# HYPNOS_BOARD_SHIELD_V1.net
KiCad netlist of a schematic drawn in EAGLE
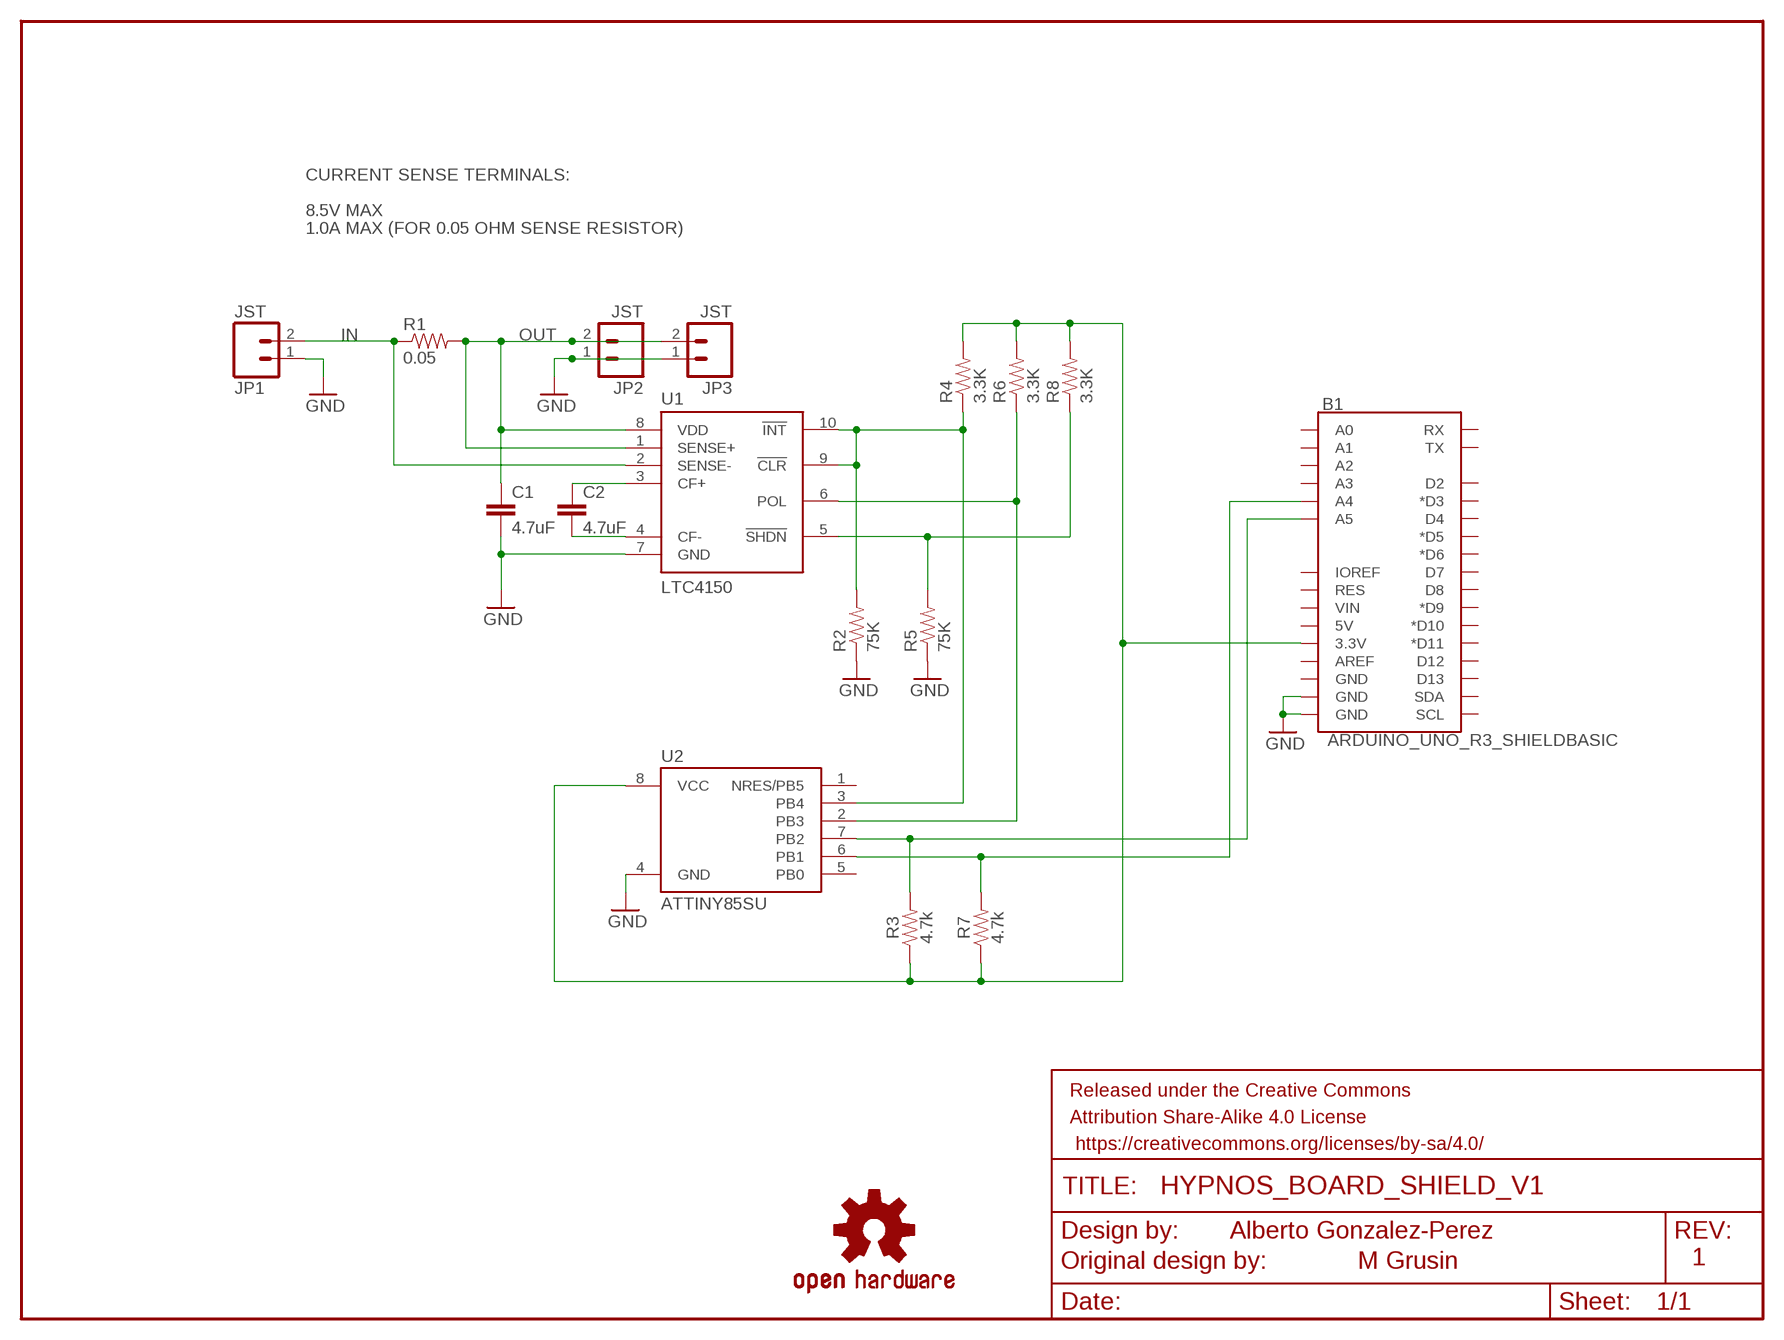
[diagram p0: schematic, sheet 1]

(export (version "E")
  (design (tool "Eeschema 10.0.6"))
  (components
    (comp (ref "B1")
      (value "ARDUINO_UNO_R3_SHIELDBASIC")
      (footprint "eagle-import:UNO_R3_SHIELD")
      (libsource (lib "eagle-import") (part "ARDUINO_UNO_R3_SHIELDBASIC"))
    )
    (comp (ref "C1")
      (value "4.7uF")
      (footprint "eagle-import:0603-CAP")
      (libsource (lib "eagle-import") (part "CAP0603-CAP"))
    )
    (comp (ref "C2")
      (value "4.7uF")
      (footprint "eagle-import:0603-CAP")
      (libsource (lib "eagle-import") (part "CAP0603-CAP"))
    )
    (comp (ref "FRAME1")
      (value "FRAME-LETTER")
      (footprint "eagle-import:CREATIVE_COMMONS")
      (libsource (lib "eagle-import") (part "FRAME-LETTER"))
    )
    (comp (ref "JP1")
      (value "JST")
      (footprint "eagle-import:JST-2-SMD")
      (libsource (lib "eagle-import") (part "M02-JST-2MM-SMT"))
    )
    (comp (ref "JP2")
      (value "JST")
      (footprint "eagle-import:JST-2-SMD")
      (libsource (lib "eagle-import") (part "M02-JST-2MM-SMT"))
    )
    (comp (ref "JP3")
      (value "JST")
      (footprint "eagle-import:JST-2-SMD")
      (libsource (lib "eagle-import") (part "M02-JST-2MM-SMT"))
    )
    (comp (ref "LOGO1")
      (value "OSHW-LOGOS")
      (footprint "eagle-import:OSHW-LOGO-S")
      (libsource (lib "eagle-import") (part "OSHW-LOGOS"))
    )
    (comp (ref "R1")
      (value "0.05")
      (footprint "eagle-import:1206")
      (libsource (lib "eagle-import") (part "RESISTOR1206"))
    )
    (comp (ref "R2")
      (value "75K")
      (footprint "eagle-import:0603-RES")
      (libsource (lib "eagle-import") (part "RESISTOR0603-RES"))
    )
    (comp (ref "R3")
      (value "4.7k")
      (footprint "eagle-import:0603")
      (libsource (lib "eagle-import") (part "4.7KOHM-0603-1/10W-1%"))
    )
    (comp (ref "R4")
      (value "3.3K")
      (footprint "eagle-import:0603-RES")
      (libsource (lib "eagle-import") (part "RESISTOR0603-RES"))
    )
    (comp (ref "R5")
      (value "75K")
      (footprint "eagle-import:0603-RES")
      (libsource (lib "eagle-import") (part "RESISTOR0603-RES"))
    )
    (comp (ref "R6")
      (value "3.3K")
      (footprint "eagle-import:0603-RES")
      (libsource (lib "eagle-import") (part "RESISTOR0603-RES"))
    )
    (comp (ref "R7")
      (value "4.7k")
      (footprint "eagle-import:0603")
      (libsource (lib "eagle-import") (part "4.7KOHM-0603-1/10W-1%"))
    )
    (comp (ref "R8")
      (value "3.3K")
      (footprint "eagle-import:0603-RES")
      (libsource (lib "eagle-import") (part "RESISTOR0603-RES"))
    )
    (comp (ref "U1")
      (value "LTC4150")
      (footprint "eagle-import:MSOP10")
      (libsource (lib "eagle-import") (part "LTC4150"))
    )
    (comp (ref "U2")
      (value "ATTINY85SU")
      (footprint "eagle-import:ATTINY85")
      (libsource (lib "eagle-import") (part "ATTINY85SU"))
    )
  )
  (nets
    (net (code "1") (name "/IN") (class "Default")
      (node (ref "JP1") (pin "2") (pinfunction "1_2") (pintype "passive"))
      (node (ref "R1") (pin "1") (pinfunction "1_1") (pintype "passive"))
      (node (ref "U1") (pin "2") (pinfunction "SENSE-_2") (pintype "bidirectional"))
    )
    (net (code "2") (name "/OUT") (class "Default")
      (node (ref "C1") (pin "1") (pinfunction "1_1") (pintype "passive"))
      (node (ref "JP2") (pin "2") (pinfunction "1_2") (pintype "passive"))
      (node (ref "JP3") (pin "2") (pinfunction "1_2") (pintype "passive"))
      (node (ref "R1") (pin "2") (pinfunction "2_2") (pintype "passive"))
      (node (ref "U1") (pin "1") (pinfunction "SENSE+_1") (pintype "bidirectional"))
      (node (ref "U1") (pin "8") (pinfunction "VDD_8") (pintype "power_in"))
    )
    (net (code "3") (name "GND") (class "Default")
      (node (ref "B1") (pin "GND@0") (pinfunction "GND_GND@0") (pintype "bidirectional"))
      (node (ref "B1") (pin "GND@1") (pinfunction "GND_GND@1") (pintype "bidirectional"))
      (node (ref "C1") (pin "2") (pinfunction "2_2") (pintype "passive"))
      (node (ref "JP1") (pin "1") (pinfunction "2_1") (pintype "passive"))
      (node (ref "JP2") (pin "1") (pinfunction "2_1") (pintype "passive"))
      (node (ref "JP3") (pin "1") (pinfunction "2_1") (pintype "passive"))
      (node (ref "R2") (pin "1") (pinfunction "1_1") (pintype "passive"))
      (node (ref "R5") (pin "1") (pinfunction "1_1") (pintype "passive"))
      (node (ref "U1") (pin "7") (pinfunction "GND_7") (pintype "power_in"))
      (node (ref "U2") (pin "4") (pinfunction "GND_4") (pintype "power_in"))
    )
    (net (code "4") (name "Net-(U1-CF+)") (class "Default")
      (node (ref "C2") (pin "1") (pinfunction "1_1") (pintype "passive"))
      (node (ref "U1") (pin "3") (pinfunction "CF+_3") (pintype "bidirectional"))
    )
    (net (code "5") (name "Net-(U1-CF-)") (class "Default")
      (node (ref "C2") (pin "2") (pinfunction "2_2") (pintype "passive"))
      (node (ref "U1") (pin "4") (pinfunction "CF-_4") (pintype "bidirectional"))
    )
    (net (code "6") (name "Net-(U1-POL)") (class "Default")
      (node (ref "R6") (pin "1") (pinfunction "1_1") (pintype "passive"))
      (node (ref "U1") (pin "6") (pinfunction "POL_6") (pintype "bidirectional"))
      (node (ref "U2") (pin "2") (pinfunction "PB3_2") (pintype "bidirectional"))
    )
    (net (code "7") (name "Net-(U1-~{CLR})") (class "Default")
      (node (ref "R2") (pin "2") (pinfunction "2_2") (pintype "passive"))
      (node (ref "R4") (pin "1") (pinfunction "1_1") (pintype "passive"))
      (node (ref "U1") (pin "10") (pinfunction "~{INT}_10") (pintype "bidirectional"))
      (node (ref "U1") (pin "9") (pinfunction "~{CLR}_9") (pintype "bidirectional"))
      (node (ref "U2") (pin "3") (pinfunction "PB4_3") (pintype "bidirectional"))
    )
    (net (code "8") (name "Net-(U1-~{SHDN})") (class "Default")
      (node (ref "R5") (pin "2") (pinfunction "2_2") (pintype "passive"))
      (node (ref "R8") (pin "1") (pinfunction "1_1") (pintype "passive"))
      (node (ref "U1") (pin "5") (pinfunction "~{SHDN}_5") (pintype "input"))
    )
    (net (code "9") (name "Net-(U2-PB1)") (class "Default")
      (node (ref "B1") (pin "A4") (pinfunction "A4_A4") (pintype "bidirectional"))
      (node (ref "R7") (pin "2") (pinfunction "2_2") (pintype "passive"))
      (node (ref "U2") (pin "6") (pinfunction "PB1_6") (pintype "bidirectional"))
    )
    (net (code "10") (name "Net-(U2-PB2)") (class "Default")
      (node (ref "B1") (pin "A5") (pinfunction "A5_A5") (pintype "bidirectional"))
      (node (ref "R3") (pin "2") (pinfunction "2_2") (pintype "passive"))
      (node (ref "U2") (pin "7") (pinfunction "PB2_7") (pintype "bidirectional"))
    )
    (net (code "11") (name "Net-(U2-VCC)") (class "Default")
      (node (ref "B1") (pin "3.3V") (pinfunction "3.3V_3.3V") (pintype "bidirectional"))
      (node (ref "R3") (pin "1") (pinfunction "1_1") (pintype "passive"))
      (node (ref "R4") (pin "2") (pinfunction "2_2") (pintype "passive"))
      (node (ref "R6") (pin "2") (pinfunction "2_2") (pintype "passive"))
      (node (ref "R7") (pin "1") (pinfunction "1_1") (pintype "passive"))
      (node (ref "R8") (pin "2") (pinfunction "2_2") (pintype "passive"))
      (node (ref "U2") (pin "8") (pinfunction "VCC_8") (pintype "power_in"))
    )
    (net (code "12") (name "unconnected-(B1-*D3-PadD3)") (class "Default")
      (node (ref "B1") (pin "D3") (pinfunction "*D3_D3") (pintype "bidirectional"))
    )
    (net (code "13") (name "unconnected-(B1-*D5-PadD5)") (class "Default")
      (node (ref "B1") (pin "D5") (pinfunction "*D5_D5") (pintype "bidirectional"))
    )
    (net (code "14") (name "unconnected-(B1-*D6-PadD6)") (class "Default")
      (node (ref "B1") (pin "D6") (pinfunction "*D6_D6") (pintype "bidirectional"))
    )
    (net (code "15") (name "unconnected-(B1-*D9-PadD9)") (class "Default")
      (node (ref "B1") (pin "D9") (pinfunction "*D9_D9") (pintype "bidirectional"))
    )
    (net (code "16") (name "unconnected-(B1-*D10-PadD10)") (class "Default")
      (node (ref "B1") (pin "D10") (pinfunction "*D10_D10") (pintype "bidirectional"))
    )
    (net (code "17") (name "unconnected-(B1-*D11-PadD11)") (class "Default")
      (node (ref "B1") (pin "D11") (pinfunction "*D11_D11") (pintype "bidirectional"))
    )
    (net (code "18") (name "unconnected-(B1-GND-PadGND@2)") (class "Default")
      (node (ref "B1") (pin "GND@2") (pinfunction "GND_GND@2") (pintype "bidirectional"))
    )
    (net (code "19") (name "unconnected-(B1-Pad5V)") (class "Default")
      (node (ref "B1") (pin "5V") (pinfunction "5V_5V") (pintype "bidirectional"))
    )
    (net (code "20") (name "unconnected-(B1-PadA0)") (class "Default")
      (node (ref "B1") (pin "A0") (pinfunction "A0_A0") (pintype "bidirectional"))
    )
    (net (code "21") (name "unconnected-(B1-PadA1)") (class "Default")
      (node (ref "B1") (pin "A1") (pinfunction "A1_A1") (pintype "bidirectional"))
    )
    (net (code "22") (name "unconnected-(B1-PadA2)") (class "Default")
      (node (ref "B1") (pin "A2") (pinfunction "A2_A2") (pintype "bidirectional"))
    )
    (net (code "23") (name "unconnected-(B1-PadA3)") (class "Default")
      (node (ref "B1") (pin "A3") (pinfunction "A3_A3") (pintype "bidirectional"))
    )
    (net (code "24") (name "unconnected-(B1-PadAREF)") (class "Default")
      (node (ref "B1") (pin "AREF") (pinfunction "AREF_AREF") (pintype "bidirectional"))
    )
    (net (code "25") (name "unconnected-(B1-PadD2)") (class "Default")
      (node (ref "B1") (pin "D2") (pinfunction "D2_D2") (pintype "bidirectional"))
    )
    (net (code "26") (name "unconnected-(B1-PadD4)") (class "Default")
      (node (ref "B1") (pin "D4") (pinfunction "D4_D4") (pintype "bidirectional"))
    )
    (net (code "27") (name "unconnected-(B1-PadD7)") (class "Default")
      (node (ref "B1") (pin "D7") (pinfunction "D7_D7") (pintype "bidirectional"))
    )
    (net (code "28") (name "unconnected-(B1-PadD8)") (class "Default")
      (node (ref "B1") (pin "D8") (pinfunction "D8_D8") (pintype "bidirectional"))
    )
    (net (code "29") (name "unconnected-(B1-PadD12)") (class "Default")
      (node (ref "B1") (pin "D12") (pinfunction "D12_D12") (pintype "bidirectional"))
    )
    (net (code "30") (name "unconnected-(B1-PadD13)") (class "Default")
      (node (ref "B1") (pin "D13") (pinfunction "D13_D13") (pintype "bidirectional"))
    )
    (net (code "31") (name "unconnected-(B1-PadIOREF)") (class "Default")
      (node (ref "B1") (pin "IOREF") (pinfunction "IOREF_IOREF") (pintype "bidirectional"))
    )
    (net (code "32") (name "unconnected-(B1-PadRES)") (class "Default")
      (node (ref "B1") (pin "RES") (pinfunction "RES_RES") (pintype "bidirectional"))
    )
    (net (code "33") (name "unconnected-(B1-PadRX)") (class "Default")
      (node (ref "B1") (pin "RX") (pinfunction "RX_RX") (pintype "bidirectional"))
    )
    (net (code "34") (name "unconnected-(B1-PadSCL)") (class "Default")
      (node (ref "B1") (pin "SCL") (pinfunction "SCL_SCL") (pintype "bidirectional"))
    )
    (net (code "35") (name "unconnected-(B1-PadSDA)") (class "Default")
      (node (ref "B1") (pin "SDA") (pinfunction "SDA_SDA") (pintype "bidirectional"))
    )
    (net (code "36") (name "unconnected-(B1-PadTX)") (class "Default")
      (node (ref "B1") (pin "TX") (pinfunction "TX_TX") (pintype "bidirectional"))
    )
    (net (code "37") (name "unconnected-(B1-PadVIN)") (class "Default")
      (node (ref "B1") (pin "VIN") (pinfunction "VIN_VIN") (pintype "bidirectional"))
    )
    (net (code "38") (name "unconnected-(U2-NRES{slash}PB5-Pad1)") (class "Default")
      (node (ref "U2") (pin "1") (pinfunction "NRES/PB5_1") (pintype "bidirectional"))
    )
    (net (code "39") (name "unconnected-(U2-PB0-Pad5)") (class "Default")
      (node (ref "U2") (pin "5") (pinfunction "PB0_5") (pintype "bidirectional"))
    )
  )
)
